# zumo_uni_spi_01.net
KiCad netlist of a schematic drawn in EAGLE
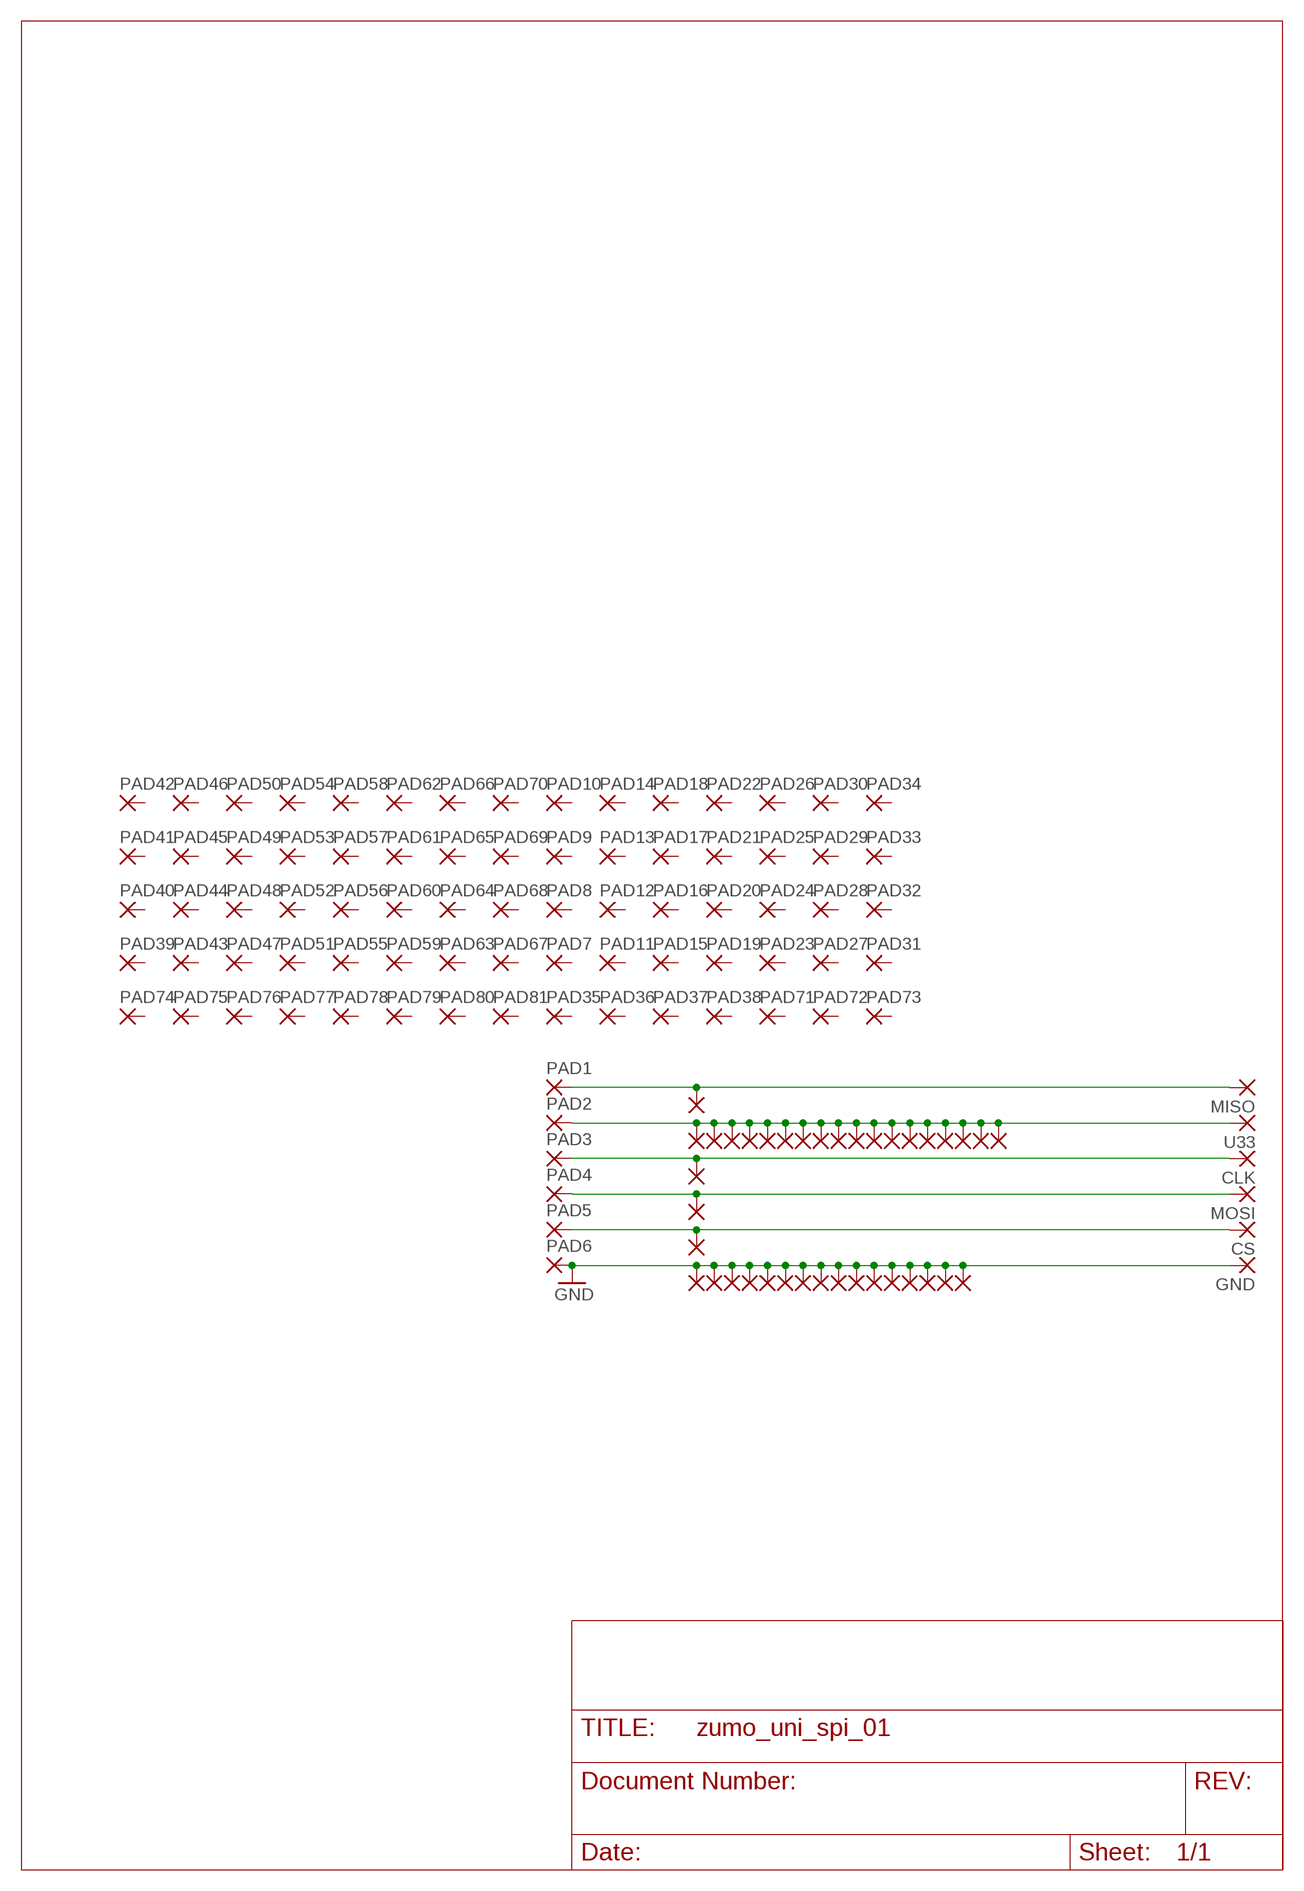
[diagram p0: schematic, sheet 1]

(export (version "E")
  (design (tool "Eeschema 10.0.6"))
  (components
    (comp (ref "CLK")
      (value "1,6/0,9")
      (footprint "eagle-import:1,6_0,9")
      (libsource (lib "eagle-import") (part "1,6/0,9"))
    )
    (comp (ref "CS")
      (value "1,6/0,9")
      (footprint "eagle-import:1,6_0,9")
      (libsource (lib "eagle-import") (part "1,6/0,9"))
    )
    (comp (ref "GND")
      (value "1,6/0,9")
      (footprint "eagle-import:1,6_0,9")
      (libsource (lib "eagle-import") (part "1,6/0,9"))
    )
    (comp (ref "MISO")
      (value "1,6/0,9")
      (footprint "eagle-import:1,6_0,9")
      (libsource (lib "eagle-import") (part "1,6/0,9"))
    )
    (comp (ref "MISO1")
      (value "1,6/0,9")
      (footprint "eagle-import:1,6_0,9")
      (libsource (lib "eagle-import") (part "1,6/0,9"))
    )
    (comp (ref "MISO2")
      (value "1,6/0,9")
      (footprint "eagle-import:1,6_0,9")
      (libsource (lib "eagle-import") (part "1,6/0,9"))
    )
    (comp (ref "MISO3")
      (value "1,6/0,9")
      (footprint "eagle-import:1,6_0,9")
      (libsource (lib "eagle-import") (part "1,6/0,9"))
    )
    (comp (ref "MISO4")
      (value "1,6/0,9")
      (footprint "eagle-import:1,6_0,9")
      (libsource (lib "eagle-import") (part "1,6/0,9"))
    )
    (comp (ref "MISO5")
      (value "1,6/0,9")
      (footprint "eagle-import:1,6_0,9")
      (libsource (lib "eagle-import") (part "1,6/0,9"))
    )
    (comp (ref "MISO6")
      (value "1,6/0,9")
      (footprint "eagle-import:1,6_0,9")
      (libsource (lib "eagle-import") (part "1,6/0,9"))
    )
    (comp (ref "MISO7")
      (value "1,6/0,9")
      (footprint "eagle-import:1,6_0,9")
      (libsource (lib "eagle-import") (part "1,6/0,9"))
    )
    (comp (ref "MISO8")
      (value "1,6/0,9")
      (footprint "eagle-import:1,6_0,9")
      (libsource (lib "eagle-import") (part "1,6/0,9"))
    )
    (comp (ref "MISO9")
      (value "1,6/0,9")
      (footprint "eagle-import:1,6_0,9")
      (libsource (lib "eagle-import") (part "1,6/0,9"))
    )
    (comp (ref "MISO10")
      (value "1,6/0,9")
      (footprint "eagle-import:1,6_0,9")
      (libsource (lib "eagle-import") (part "1,6/0,9"))
    )
    (comp (ref "MISO11")
      (value "1,6/0,9")
      (footprint "eagle-import:1,6_0,9")
      (libsource (lib "eagle-import") (part "1,6/0,9"))
    )
    (comp (ref "MISO12")
      (value "1,6/0,9")
      (footprint "eagle-import:1,6_0,9")
      (libsource (lib "eagle-import") (part "1,6/0,9"))
    )
    (comp (ref "MISO13")
      (value "1,6/0,9")
      (footprint "eagle-import:1,6_0,9")
      (libsource (lib "eagle-import") (part "1,6/0,9"))
    )
    (comp (ref "MISO14")
      (value "1,6/0,9")
      (footprint "eagle-import:1,6_0,9")
      (libsource (lib "eagle-import") (part "1,6/0,9"))
    )
    (comp (ref "MISO15")
      (value "1,6/0,9")
      (footprint "eagle-import:1,6_0,9")
      (libsource (lib "eagle-import") (part "1,6/0,9"))
    )
    (comp (ref "MISO16")
      (value "1,6/0,9")
      (footprint "eagle-import:1,6_0,9")
      (libsource (lib "eagle-import") (part "1,6/0,9"))
    )
    (comp (ref "MISO17")
      (value "1,6/0,9")
      (footprint "eagle-import:1,6_0,9")
      (libsource (lib "eagle-import") (part "1,6/0,9"))
    )
    (comp (ref "MISO18")
      (value "1,6/0,9")
      (footprint "eagle-import:1,6_0,9")
      (libsource (lib "eagle-import") (part "1,6/0,9"))
    )
    (comp (ref "MISO19")
      (value "1,6/0,9")
      (footprint "eagle-import:1,6_0,9")
      (libsource (lib "eagle-import") (part "1,6/0,9"))
    )
    (comp (ref "MISO20")
      (value "1,6/0,9")
      (footprint "eagle-import:1,6_0,9")
      (libsource (lib "eagle-import") (part "1,6/0,9"))
    )
    (comp (ref "MISO21")
      (value "1,6/0,9")
      (footprint "eagle-import:1,6_0,9")
      (libsource (lib "eagle-import") (part "1,6/0,9"))
    )
    (comp (ref "MISO22")
      (value "1,6/0,9")
      (footprint "eagle-import:1,6_0,9")
      (libsource (lib "eagle-import") (part "1,6/0,9"))
    )
    (comp (ref "MISO23")
      (value "1,6/0,9")
      (footprint "eagle-import:1,6_0,9")
      (libsource (lib "eagle-import") (part "1,6/0,9"))
    )
    (comp (ref "MISO24")
      (value "1,6/0,9")
      (footprint "eagle-import:1,6_0,9")
      (libsource (lib "eagle-import") (part "1,6/0,9"))
    )
    (comp (ref "MISO25")
      (value "1,6/0,9")
      (footprint "eagle-import:1,6_0,9")
      (libsource (lib "eagle-import") (part "1,6/0,9"))
    )
    (comp (ref "MISO26")
      (value "1,6/0,9")
      (footprint "eagle-import:1,6_0,9")
      (libsource (lib "eagle-import") (part "1,6/0,9"))
    )
    (comp (ref "MISO27")
      (value "1,6/0,9")
      (footprint "eagle-import:1,6_0,9")
      (libsource (lib "eagle-import") (part "1,6/0,9"))
    )
    (comp (ref "MISO28")
      (value "1,6/0,9")
      (footprint "eagle-import:1,6_0,9")
      (libsource (lib "eagle-import") (part "1,6/0,9"))
    )
    (comp (ref "MISO29")
      (value "1,6/0,9")
      (footprint "eagle-import:1,6_0,9")
      (libsource (lib "eagle-import") (part "1,6/0,9"))
    )
    (comp (ref "MISO30")
      (value "1,6/0,9")
      (footprint "eagle-import:1,6_0,9")
      (libsource (lib "eagle-import") (part "1,6/0,9"))
    )
    (comp (ref "MISO31")
      (value "1,6/0,9")
      (footprint "eagle-import:1,6_0,9")
      (libsource (lib "eagle-import") (part "1,6/0,9"))
    )
    (comp (ref "MISO32")
      (value "1,6/0,9")
      (footprint "eagle-import:1,6_0,9")
      (libsource (lib "eagle-import") (part "1,6/0,9"))
    )
    (comp (ref "MISO33")
      (value "1,6/0,9")
      (footprint "eagle-import:1,6_0,9")
      (libsource (lib "eagle-import") (part "1,6/0,9"))
    )
    (comp (ref "MISO34")
      (value "1,6/0,9")
      (footprint "eagle-import:1,6_0,9")
      (libsource (lib "eagle-import") (part "1,6/0,9"))
    )
    (comp (ref "MISO35")
      (value "1,6/0,9")
      (footprint "eagle-import:1,6_0,9")
      (libsource (lib "eagle-import") (part "1,6/0,9"))
    )
    (comp (ref "MISO36")
      (value "1,6/0,9")
      (footprint "eagle-import:1,6_0,9")
      (libsource (lib "eagle-import") (part "1,6/0,9"))
    )
    (comp (ref "MISO37")
      (value "1,6/0,9")
      (footprint "eagle-import:1,6_0,9")
      (libsource (lib "eagle-import") (part "1,6/0,9"))
    )
    (comp (ref "MISO38")
      (value "1,6/0,9")
      (footprint "eagle-import:1,6_0,9")
      (libsource (lib "eagle-import") (part "1,6/0,9"))
    )
    (comp (ref "MOSI")
      (value "1,6/0,9")
      (footprint "eagle-import:1,6_0,9")
      (libsource (lib "eagle-import") (part "1,6/0,9"))
    )
    (comp (ref "PAD1")
      (value "SMD2")
      (footprint "eagle-import:SMD1,27-2,54")
      (libsource (lib "eagle-import") (part "SMD2"))
    )
    (comp (ref "PAD2")
      (value "SMD2")
      (footprint "eagle-import:SMD1,27-2,54")
      (libsource (lib "eagle-import") (part "SMD2"))
    )
    (comp (ref "PAD3")
      (value "SMD2")
      (footprint "eagle-import:SMD1,27-2,54")
      (libsource (lib "eagle-import") (part "SMD2"))
    )
    (comp (ref "PAD4")
      (value "SMD2")
      (footprint "eagle-import:SMD1,27-2,54")
      (libsource (lib "eagle-import") (part "SMD2"))
    )
    (comp (ref "PAD5")
      (value "SMD2")
      (footprint "eagle-import:SMD1,27-2,54")
      (libsource (lib "eagle-import") (part "SMD2"))
    )
    (comp (ref "PAD6")
      (value "SMD2")
      (footprint "eagle-import:SMD1,27-2,54")
      (libsource (lib "eagle-import") (part "SMD2"))
    )
    (comp (ref "PAD7")
      (value "1,6/0,9")
      (footprint "eagle-import:1,6_0,9")
      (libsource (lib "eagle-import") (part "1,6/0,9"))
    )
    (comp (ref "PAD8")
      (value "1,6/0,9")
      (footprint "eagle-import:1,6_0,9")
      (libsource (lib "eagle-import") (part "1,6/0,9"))
    )
    (comp (ref "PAD9")
      (value "1,6/0,9")
      (footprint "eagle-import:1,6_0,9")
      (libsource (lib "eagle-import") (part "1,6/0,9"))
    )
    (comp (ref "PAD10")
      (value "1,6/0,9")
      (footprint "eagle-import:1,6_0,9")
      (libsource (lib "eagle-import") (part "1,6/0,9"))
    )
    (comp (ref "PAD11")
      (value "1,6/0,9")
      (footprint "eagle-import:1,6_0,9")
      (libsource (lib "eagle-import") (part "1,6/0,9"))
    )
    (comp (ref "PAD12")
      (value "1,6/0,9")
      (footprint "eagle-import:1,6_0,9")
      (libsource (lib "eagle-import") (part "1,6/0,9"))
    )
    (comp (ref "PAD13")
      (value "1,6/0,9")
      (footprint "eagle-import:1,6_0,9")
      (libsource (lib "eagle-import") (part "1,6/0,9"))
    )
    (comp (ref "PAD14")
      (value "1,6/0,9")
      (footprint "eagle-import:1,6_0,9")
      (libsource (lib "eagle-import") (part "1,6/0,9"))
    )
    (comp (ref "PAD15")
      (value "1,6/0,9")
      (footprint "eagle-import:1,6_0,9")
      (libsource (lib "eagle-import") (part "1,6/0,9"))
    )
    (comp (ref "PAD16")
      (value "1,6/0,9")
      (footprint "eagle-import:1,6_0,9")
      (libsource (lib "eagle-import") (part "1,6/0,9"))
    )
    (comp (ref "PAD17")
      (value "1,6/0,9")
      (footprint "eagle-import:1,6_0,9")
      (libsource (lib "eagle-import") (part "1,6/0,9"))
    )
    (comp (ref "PAD18")
      (value "1,6/0,9")
      (footprint "eagle-import:1,6_0,9")
      (libsource (lib "eagle-import") (part "1,6/0,9"))
    )
    (comp (ref "PAD19")
      (value "1,6/0,9")
      (footprint "eagle-import:1,6_0,9")
      (libsource (lib "eagle-import") (part "1,6/0,9"))
    )
    (comp (ref "PAD20")
      (value "1,6/0,9")
      (footprint "eagle-import:1,6_0,9")
      (libsource (lib "eagle-import") (part "1,6/0,9"))
    )
    (comp (ref "PAD21")
      (value "1,6/0,9")
      (footprint "eagle-import:1,6_0,9")
      (libsource (lib "eagle-import") (part "1,6/0,9"))
    )
    (comp (ref "PAD22")
      (value "1,6/0,9")
      (footprint "eagle-import:1,6_0,9")
      (libsource (lib "eagle-import") (part "1,6/0,9"))
    )
    (comp (ref "PAD23")
      (value "1,6/0,9")
      (footprint "eagle-import:1,6_0,9")
      (libsource (lib "eagle-import") (part "1,6/0,9"))
    )
    (comp (ref "PAD24")
      (value "1,6/0,9")
      (footprint "eagle-import:1,6_0,9")
      (libsource (lib "eagle-import") (part "1,6/0,9"))
    )
    (comp (ref "PAD25")
      (value "1,6/0,9")
      (footprint "eagle-import:1,6_0,9")
      (libsource (lib "eagle-import") (part "1,6/0,9"))
    )
    (comp (ref "PAD26")
      (value "1,6/0,9")
      (footprint "eagle-import:1,6_0,9")
      (libsource (lib "eagle-import") (part "1,6/0,9"))
    )
    (comp (ref "PAD27")
      (value "1,6/0,9")
      (footprint "eagle-import:1,6_0,9")
      (libsource (lib "eagle-import") (part "1,6/0,9"))
    )
    (comp (ref "PAD28")
      (value "1,6/0,9")
      (footprint "eagle-import:1,6_0,9")
      (libsource (lib "eagle-import") (part "1,6/0,9"))
    )
    (comp (ref "PAD29")
      (value "1,6/0,9")
      (footprint "eagle-import:1,6_0,9")
      (libsource (lib "eagle-import") (part "1,6/0,9"))
    )
    (comp (ref "PAD30")
      (value "1,6/0,9")
      (footprint "eagle-import:1,6_0,9")
      (libsource (lib "eagle-import") (part "1,6/0,9"))
    )
    (comp (ref "PAD31")
      (value "1,6/0,9")
      (footprint "eagle-import:1,6_0,9")
      (libsource (lib "eagle-import") (part "1,6/0,9"))
    )
    (comp (ref "PAD32")
      (value "1,6/0,9")
      (footprint "eagle-import:1,6_0,9")
      (libsource (lib "eagle-import") (part "1,6/0,9"))
    )
    (comp (ref "PAD33")
      (value "1,6/0,9")
      (footprint "eagle-import:1,6_0,9")
      (libsource (lib "eagle-import") (part "1,6/0,9"))
    )
    (comp (ref "PAD34")
      (value "1,6/0,9")
      (footprint "eagle-import:1,6_0,9")
      (libsource (lib "eagle-import") (part "1,6/0,9"))
    )
    (comp (ref "PAD35")
      (value "1,6/0,9")
      (footprint "eagle-import:1,6_0,9")
      (libsource (lib "eagle-import") (part "1,6/0,9"))
    )
    (comp (ref "PAD36")
      (value "1,6/0,9")
      (footprint "eagle-import:1,6_0,9")
      (libsource (lib "eagle-import") (part "1,6/0,9"))
    )
    (comp (ref "PAD37")
      (value "1,6/0,9")
      (footprint "eagle-import:1,6_0,9")
      (libsource (lib "eagle-import") (part "1,6/0,9"))
    )
    (comp (ref "PAD38")
      (value "1,6/0,9")
      (footprint "eagle-import:1,6_0,9")
      (libsource (lib "eagle-import") (part "1,6/0,9"))
    )
    (comp (ref "PAD39")
      (value "1,6/0,9")
      (footprint "eagle-import:1,6_0,9")
      (libsource (lib "eagle-import") (part "1,6/0,9"))
    )
    (comp (ref "PAD40")
      (value "1,6/0,9")
      (footprint "eagle-import:1,6_0,9")
      (libsource (lib "eagle-import") (part "1,6/0,9"))
    )
    (comp (ref "PAD41")
      (value "1,6/0,9")
      (footprint "eagle-import:1,6_0,9")
      (libsource (lib "eagle-import") (part "1,6/0,9"))
    )
    (comp (ref "PAD42")
      (value "1,6/0,9")
      (footprint "eagle-import:1,6_0,9")
      (libsource (lib "eagle-import") (part "1,6/0,9"))
    )
    (comp (ref "PAD43")
      (value "1,6/0,9")
      (footprint "eagle-import:1,6_0,9")
      (libsource (lib "eagle-import") (part "1,6/0,9"))
    )
    (comp (ref "PAD44")
      (value "1,6/0,9")
      (footprint "eagle-import:1,6_0,9")
      (libsource (lib "eagle-import") (part "1,6/0,9"))
    )
    (comp (ref "PAD45")
      (value "1,6/0,9")
      (footprint "eagle-import:1,6_0,9")
      (libsource (lib "eagle-import") (part "1,6/0,9"))
    )
    (comp (ref "PAD46")
      (value "1,6/0,9")
      (footprint "eagle-import:1,6_0,9")
      (libsource (lib "eagle-import") (part "1,6/0,9"))
    )
    (comp (ref "PAD47")
      (value "1,6/0,9")
      (footprint "eagle-import:1,6_0,9")
      (libsource (lib "eagle-import") (part "1,6/0,9"))
    )
    (comp (ref "PAD48")
      (value "1,6/0,9")
      (footprint "eagle-import:1,6_0,9")
      (libsource (lib "eagle-import") (part "1,6/0,9"))
    )
    (comp (ref "PAD49")
      (value "1,6/0,9")
      (footprint "eagle-import:1,6_0,9")
      (libsource (lib "eagle-import") (part "1,6/0,9"))
    )
    (comp (ref "PAD50")
      (value "1,6/0,9")
      (footprint "eagle-import:1,6_0,9")
      (libsource (lib "eagle-import") (part "1,6/0,9"))
    )
    (comp (ref "PAD51")
      (value "1,6/0,9")
      (footprint "eagle-import:1,6_0,9")
      (libsource (lib "eagle-import") (part "1,6/0,9"))
    )
    (comp (ref "PAD52")
      (value "1,6/0,9")
      (footprint "eagle-import:1,6_0,9")
      (libsource (lib "eagle-import") (part "1,6/0,9"))
    )
    (comp (ref "PAD53")
      (value "1,6/0,9")
      (footprint "eagle-import:1,6_0,9")
      (libsource (lib "eagle-import") (part "1,6/0,9"))
    )
    (comp (ref "PAD54")
      (value "1,6/0,9")
      (footprint "eagle-import:1,6_0,9")
      (libsource (lib "eagle-import") (part "1,6/0,9"))
    )
    (comp (ref "PAD55")
      (value "1,6/0,9")
      (footprint "eagle-import:1,6_0,9")
      (libsource (lib "eagle-import") (part "1,6/0,9"))
    )
    (comp (ref "PAD56")
      (value "1,6/0,9")
      (footprint "eagle-import:1,6_0,9")
      (libsource (lib "eagle-import") (part "1,6/0,9"))
    )
    (comp (ref "PAD57")
      (value "1,6/0,9")
      (footprint "eagle-import:1,6_0,9")
      (libsource (lib "eagle-import") (part "1,6/0,9"))
    )
    (comp (ref "PAD58")
      (value "1,6/0,9")
      (footprint "eagle-import:1,6_0,9")
      (libsource (lib "eagle-import") (part "1,6/0,9"))
    )
    (comp (ref "PAD59")
      (value "1,6/0,9")
      (footprint "eagle-import:1,6_0,9")
      (libsource (lib "eagle-import") (part "1,6/0,9"))
    )
    (comp (ref "PAD60")
      (value "1,6/0,9")
      (footprint "eagle-import:1,6_0,9")
      (libsource (lib "eagle-import") (part "1,6/0,9"))
    )
    (comp (ref "PAD61")
      (value "1,6/0,9")
      (footprint "eagle-import:1,6_0,9")
      (libsource (lib "eagle-import") (part "1,6/0,9"))
    )
    (comp (ref "PAD62")
      (value "1,6/0,9")
      (footprint "eagle-import:1,6_0,9")
      (libsource (lib "eagle-import") (part "1,6/0,9"))
    )
    (comp (ref "PAD63")
      (value "1,6/0,9")
      (footprint "eagle-import:1,6_0,9")
      (libsource (lib "eagle-import") (part "1,6/0,9"))
    )
    (comp (ref "PAD64")
      (value "1,6/0,9")
      (footprint "eagle-import:1,6_0,9")
      (libsource (lib "eagle-import") (part "1,6/0,9"))
    )
    (comp (ref "PAD65")
      (value "1,6/0,9")
      (footprint "eagle-import:1,6_0,9")
      (libsource (lib "eagle-import") (part "1,6/0,9"))
    )
    (comp (ref "PAD66")
      (value "1,6/0,9")
      (footprint "eagle-import:1,6_0,9")
      (libsource (lib "eagle-import") (part "1,6/0,9"))
    )
    (comp (ref "PAD67")
      (value "1,6/0,9")
      (footprint "eagle-import:1,6_0,9")
      (libsource (lib "eagle-import") (part "1,6/0,9"))
    )
    (comp (ref "PAD68")
      (value "1,6/0,9")
      (footprint "eagle-import:1,6_0,9")
      (libsource (lib "eagle-import") (part "1,6/0,9"))
    )
    (comp (ref "PAD69")
      (value "1,6/0,9")
      (footprint "eagle-import:1,6_0,9")
      (libsource (lib "eagle-import") (part "1,6/0,9"))
    )
    (comp (ref "PAD70")
      (value "1,6/0,9")
      (footprint "eagle-import:1,6_0,9")
      (libsource (lib "eagle-import") (part "1,6/0,9"))
    )
    (comp (ref "PAD71")
      (value "1,6/0,9")
      (footprint "eagle-import:1,6_0,9")
      (libsource (lib "eagle-import") (part "1,6/0,9"))
    )
    (comp (ref "PAD72")
      (value "1,6/0,9")
      (footprint "eagle-import:1,6_0,9")
      (libsource (lib "eagle-import") (part "1,6/0,9"))
    )
    (comp (ref "PAD73")
      (value "1,6/0,9")
      (footprint "eagle-import:1,6_0,9")
      (libsource (lib "eagle-import") (part "1,6/0,9"))
    )
    (comp (ref "PAD74")
      (value "1,6/0,9")
      (footprint "eagle-import:1,6_0,9")
      (libsource (lib "eagle-import") (part "1,6/0,9"))
    )
    (comp (ref "PAD75")
      (value "1,6/0,9")
      (footprint "eagle-import:1,6_0,9")
      (libsource (lib "eagle-import") (part "1,6/0,9"))
    )
    (comp (ref "PAD76")
      (value "1,6/0,9")
      (footprint "eagle-import:1,6_0,9")
      (libsource (lib "eagle-import") (part "1,6/0,9"))
    )
    (comp (ref "PAD77")
      (value "1,6/0,9")
      (footprint "eagle-import:1,6_0,9")
      (libsource (lib "eagle-import") (part "1,6/0,9"))
    )
    (comp (ref "PAD78")
      (value "1,6/0,9")
      (footprint "eagle-import:1,6_0,9")
      (libsource (lib "eagle-import") (part "1,6/0,9"))
    )
    (comp (ref "PAD79")
      (value "1,6/0,9")
      (footprint "eagle-import:1,6_0,9")
      (libsource (lib "eagle-import") (part "1,6/0,9"))
    )
    (comp (ref "PAD80")
      (value "1,6/0,9")
      (footprint "eagle-import:1,6_0,9")
      (libsource (lib "eagle-import") (part "1,6/0,9"))
    )
    (comp (ref "PAD81")
      (value "1,6/0,9")
      (footprint "eagle-import:1,6_0,9")
      (libsource (lib "eagle-import") (part "1,6/0,9"))
    )
    (comp (ref "U33")
      (value "1,6/0,9")
      (footprint "eagle-import:1,6_0,9")
      (libsource (lib "eagle-import") (part "1,6/0,9"))
    )
  )
  (nets
    (net (code "1") (name "GND") (class "Default")
      (node (ref "GND") (pin "1") (pinfunction "P_1") (pintype "passive"))
      (node (ref "MISO10") (pin "1") (pinfunction "P_1") (pintype "passive"))
      (node (ref "MISO11") (pin "1") (pinfunction "P_1") (pintype "passive"))
      (node (ref "MISO12") (pin "1") (pinfunction "P_1") (pintype "passive"))
      (node (ref "MISO13") (pin "1") (pinfunction "P_1") (pintype "passive"))
      (node (ref "MISO14") (pin "1") (pinfunction "P_1") (pintype "passive"))
      (node (ref "MISO15") (pin "1") (pinfunction "P_1") (pintype "passive"))
      (node (ref "MISO16") (pin "1") (pinfunction "P_1") (pintype "passive"))
      (node (ref "MISO17") (pin "1") (pinfunction "P_1") (pintype "passive"))
      (node (ref "MISO18") (pin "1") (pinfunction "P_1") (pintype "passive"))
      (node (ref "MISO19") (pin "1") (pinfunction "P_1") (pintype "passive"))
      (node (ref "MISO20") (pin "1") (pinfunction "P_1") (pintype "passive"))
      (node (ref "MISO5") (pin "1") (pinfunction "P_1") (pintype "passive"))
      (node (ref "MISO6") (pin "1") (pinfunction "P_1") (pintype "passive"))
      (node (ref "MISO7") (pin "1") (pinfunction "P_1") (pintype "passive"))
      (node (ref "MISO8") (pin "1") (pinfunction "P_1") (pintype "passive"))
      (node (ref "MISO9") (pin "1") (pinfunction "P_1") (pintype "passive"))
      (node (ref "PAD6") (pin "1") (pinfunction "P_1") (pintype "passive"))
    )
    (net (code "2") (name "Net-(CLK-P)") (class "Default")
      (node (ref "CLK") (pin "1") (pinfunction "P_1") (pintype "passive"))
      (node (ref "MISO3") (pin "1") (pinfunction "P_1") (pintype "passive"))
      (node (ref "PAD3") (pin "1") (pinfunction "P_1") (pintype "passive"))
    )
    (net (code "3") (name "Net-(CS-P)") (class "Default")
      (node (ref "CS") (pin "1") (pinfunction "P_1") (pintype "passive"))
      (node (ref "MISO1") (pin "1") (pinfunction "P_1") (pintype "passive"))
      (node (ref "PAD5") (pin "1") (pinfunction "P_1") (pintype "passive"))
    )
    (net (code "4") (name "Net-(MISO-P)") (class "Default")
      (node (ref "MISO") (pin "1") (pinfunction "P_1") (pintype "passive"))
      (node (ref "MISO21") (pin "1") (pinfunction "P_1") (pintype "passive"))
      (node (ref "PAD1") (pin "1") (pinfunction "P_1") (pintype "passive"))
    )
    (net (code "5") (name "Net-(MISO2-P)") (class "Default")
      (node (ref "MISO2") (pin "1") (pinfunction "P_1") (pintype "passive"))
      (node (ref "MOSI") (pin "1") (pinfunction "P_1") (pintype "passive"))
      (node (ref "PAD4") (pin "1") (pinfunction "P_1") (pintype "passive"))
    )
    (net (code "6") (name "Net-(MISO22-P)") (class "Default")
      (node (ref "MISO22") (pin "1") (pinfunction "P_1") (pintype "passive"))
      (node (ref "MISO23") (pin "1") (pinfunction "P_1") (pintype "passive"))
      (node (ref "MISO24") (pin "1") (pinfunction "P_1") (pintype "passive"))
      (node (ref "MISO25") (pin "1") (pinfunction "P_1") (pintype "passive"))
      (node (ref "MISO26") (pin "1") (pinfunction "P_1") (pintype "passive"))
      (node (ref "MISO27") (pin "1") (pinfunction "P_1") (pintype "passive"))
      (node (ref "MISO28") (pin "1") (pinfunction "P_1") (pintype "passive"))
      (node (ref "MISO29") (pin "1") (pinfunction "P_1") (pintype "passive"))
      (node (ref "MISO30") (pin "1") (pinfunction "P_1") (pintype "passive"))
      (node (ref "MISO31") (pin "1") (pinfunction "P_1") (pintype "passive"))
      (node (ref "MISO32") (pin "1") (pinfunction "P_1") (pintype "passive"))
      (node (ref "MISO33") (pin "1") (pinfunction "P_1") (pintype "passive"))
      (node (ref "MISO34") (pin "1") (pinfunction "P_1") (pintype "passive"))
      (node (ref "MISO35") (pin "1") (pinfunction "P_1") (pintype "passive"))
      (node (ref "MISO36") (pin "1") (pinfunction "P_1") (pintype "passive"))
      (node (ref "MISO37") (pin "1") (pinfunction "P_1") (pintype "passive"))
      (node (ref "MISO38") (pin "1") (pinfunction "P_1") (pintype "passive"))
      (node (ref "MISO4") (pin "1") (pinfunction "P_1") (pintype "passive"))
      (node (ref "PAD2") (pin "1") (pinfunction "P_1") (pintype "passive"))
      (node (ref "U33") (pin "1") (pinfunction "P_1") (pintype "passive"))
    )
    (net (code "7") (name "unconnected-(PAD7-P-Pad1)") (class "Default")
      (node (ref "PAD7") (pin "1") (pinfunction "P_1") (pintype "passive"))
    )
    (net (code "8") (name "unconnected-(PAD8-P-Pad1)") (class "Default")
      (node (ref "PAD8") (pin "1") (pinfunction "P_1") (pintype "passive"))
    )
    (net (code "9") (name "unconnected-(PAD9-P-Pad1)") (class "Default")
      (node (ref "PAD9") (pin "1") (pinfunction "P_1") (pintype "passive"))
    )
    (net (code "10") (name "unconnected-(PAD10-P-Pad1)") (class "Default")
      (node (ref "PAD10") (pin "1") (pinfunction "P_1") (pintype "passive"))
    )
    (net (code "11") (name "unconnected-(PAD11-P-Pad1)") (class "Default")
      (node (ref "PAD11") (pin "1") (pinfunction "P_1") (pintype "passive"))
    )
    (net (code "12") (name "unconnected-(PAD12-P-Pad1)") (class "Default")
      (node (ref "PAD12") (pin "1") (pinfunction "P_1") (pintype "passive"))
    )
    (net (code "13") (name "unconnected-(PAD13-P-Pad1)") (class "Default")
      (node (ref "PAD13") (pin "1") (pinfunction "P_1") (pintype "passive"))
    )
    (net (code "14") (name "unconnected-(PAD14-P-Pad1)") (class "Default")
      (node (ref "PAD14") (pin "1") (pinfunction "P_1") (pintype "passive"))
    )
    (net (code "15") (name "unconnected-(PAD15-P-Pad1)") (class "Default")
      (node (ref "PAD15") (pin "1") (pinfunction "P_1") (pintype "passive"))
    )
    (net (code "16") (name "unconnected-(PAD16-P-Pad1)") (class "Default")
      (node (ref "PAD16") (pin "1") (pinfunction "P_1") (pintype "passive"))
    )
    (net (code "17") (name "unconnected-(PAD17-P-Pad1)") (class "Default")
      (node (ref "PAD17") (pin "1") (pinfunction "P_1") (pintype "passive"))
    )
    (net (code "18") (name "unconnected-(PAD18-P-Pad1)") (class "Default")
      (node (ref "PAD18") (pin "1") (pinfunction "P_1") (pintype "passive"))
    )
    (net (code "19") (name "unconnected-(PAD19-P-Pad1)") (class "Default")
      (node (ref "PAD19") (pin "1") (pinfunction "P_1") (pintype "passive"))
    )
    (net (code "20") (name "unconnected-(PAD20-P-Pad1)") (class "Default")
      (node (ref "PAD20") (pin "1") (pinfunction "P_1") (pintype "passive"))
    )
    (net (code "21") (name "unconnected-(PAD21-P-Pad1)") (class "Default")
      (node (ref "PAD21") (pin "1") (pinfunction "P_1") (pintype "passive"))
    )
    (net (code "22") (name "unconnected-(PAD22-P-Pad1)") (class "Default")
      (node (ref "PAD22") (pin "1") (pinfunction "P_1") (pintype "passive"))
    )
    (net (code "23") (name "unconnected-(PAD23-P-Pad1)") (class "Default")
      (node (ref "PAD23") (pin "1") (pinfunction "P_1") (pintype "passive"))
    )
    (net (code "24") (name "unconnected-(PAD24-P-Pad1)") (class "Default")
      (node (ref "PAD24") (pin "1") (pinfunction "P_1") (pintype "passive"))
    )
    (net (code "25") (name "unconnected-(PAD25-P-Pad1)") (class "Default")
      (node (ref "PAD25") (pin "1") (pinfunction "P_1") (pintype "passive"))
    )
    (net (code "26") (name "unconnected-(PAD26-P-Pad1)") (class "Default")
      (node (ref "PAD26") (pin "1") (pinfunction "P_1") (pintype "passive"))
    )
    (net (code "27") (name "unconnected-(PAD27-P-Pad1)") (class "Default")
      (node (ref "PAD27") (pin "1") (pinfunction "P_1") (pintype "passive"))
    )
    (net (code "28") (name "unconnected-(PAD28-P-Pad1)") (class "Default")
      (node (ref "PAD28") (pin "1") (pinfunction "P_1") (pintype "passive"))
    )
    (net (code "29") (name "unconnected-(PAD29-P-Pad1)") (class "Default")
      (node (ref "PAD29") (pin "1") (pinfunction "P_1") (pintype "passive"))
    )
    (net (code "30") (name "unconnected-(PAD30-P-Pad1)") (class "Default")
      (node (ref "PAD30") (pin "1") (pinfunction "P_1") (pintype "passive"))
    )
    (net (code "31") (name "unconnected-(PAD31-P-Pad1)") (class "Default")
      (node (ref "PAD31") (pin "1") (pinfunction "P_1") (pintype "passive"))
    )
    (net (code "32") (name "unconnected-(PAD32-P-Pad1)") (class "Default")
      (node (ref "PAD32") (pin "1") (pinfunction "P_1") (pintype "passive"))
    )
    (net (code "33") (name "unconnected-(PAD33-P-Pad1)") (class "Default")
      (node (ref "PAD33") (pin "1") (pinfunction "P_1") (pintype "passive"))
    )
    (net (code "34") (name "unconnected-(PAD34-P-Pad1)") (class "Default")
      (node (ref "PAD34") (pin "1") (pinfunction "P_1") (pintype "passive"))
    )
    (net (code "35") (name "unconnected-(PAD35-P-Pad1)") (class "Default")
      (node (ref "PAD35") (pin "1") (pinfunction "P_1") (pintype "passive"))
    )
    (net (code "36") (name "unconnected-(PAD36-P-Pad1)") (class "Default")
      (node (ref "PAD36") (pin "1") (pinfunction "P_1") (pintype "passive"))
    )
    (net (code "37") (name "unconnected-(PAD37-P-Pad1)") (class "Default")
      (node (ref "PAD37") (pin "1") (pinfunction "P_1") (pintype "passive"))
    )
    (net (code "38") (name "unconnected-(PAD38-P-Pad1)") (class "Default")
      (node (ref "PAD38") (pin "1") (pinfunction "P_1") (pintype "passive"))
    )
    (net (code "39") (name "unconnected-(PAD39-P-Pad1)") (class "Default")
      (node (ref "PAD39") (pin "1") (pinfunction "P_1") (pintype "passive"))
    )
    (net (code "40") (name "unconnected-(PAD40-P-Pad1)") (class "Default")
      (node (ref "PAD40") (pin "1") (pinfunction "P_1") (pintype "passive"))
    )
    (net (code "41") (name "unconnected-(PAD41-P-Pad1)") (class "Default")
      (node (ref "PAD41") (pin "1") (pinfunction "P_1") (pintype "passive"))
    )
    (net (code "42") (name "unconnected-(PAD42-P-Pad1)") (class "Default")
      (node (ref "PAD42") (pin "1") (pinfunction "P_1") (pintype "passive"))
    )
    (net (code "43") (name "unconnected-(PAD43-P-Pad1)") (class "Default")
      (node (ref "PAD43") (pin "1") (pinfunction "P_1") (pintype "passive"))
    )
    (net (code "44") (name "unconnected-(PAD44-P-Pad1)") (class "Default")
      (node (ref "PAD44") (pin "1") (pinfunction "P_1") (pintype "passive"))
    )
    (net (code "45") (name "unconnected-(PAD45-P-Pad1)") (class "Default")
      (node (ref "PAD45") (pin "1") (pinfunction "P_1") (pintype "passive"))
    )
    (net (code "46") (name "unconnected-(PAD46-P-Pad1)") (class "Default")
      (node (ref "PAD46") (pin "1") (pinfunction "P_1") (pintype "passive"))
    )
    (net (code "47") (name "unconnected-(PAD47-P-Pad1)") (class "Default")
      (node (ref "PAD47") (pin "1") (pinfunction "P_1") (pintype "passive"))
    )
    (net (code "48") (name "unconnected-(PAD48-P-Pad1)") (class "Default")
      (node (ref "PAD48") (pin "1") (pinfunction "P_1") (pintype "passive"))
    )
    (net (code "49") (name "unconnected-(PAD49-P-Pad1)") (class "Default")
      (node (ref "PAD49") (pin "1") (pinfunction "P_1") (pintype "passive"))
    )
    (net (code "50") (name "unconnected-(PAD50-P-Pad1)") (class "Default")
      (node (ref "PAD50") (pin "1") (pinfunction "P_1") (pintype "passive"))
    )
    (net (code "51") (name "unconnected-(PAD51-P-Pad1)") (class "Default")
      (node (ref "PAD51") (pin "1") (pinfunction "P_1") (pintype "passive"))
    )
    (net (code "52") (name "unconnected-(PAD52-P-Pad1)") (class "Default")
      (node (ref "PAD52") (pin "1") (pinfunction "P_1") (pintype "passive"))
    )
    (net (code "53") (name "unconnected-(PAD53-P-Pad1)") (class "Default")
      (node (ref "PAD53") (pin "1") (pinfunction "P_1") (pintype "passive"))
    )
    (net (code "54") (name "unconnected-(PAD54-P-Pad1)") (class "Default")
      (node (ref "PAD54") (pin "1") (pinfunction "P_1") (pintype "passive"))
    )
    (net (code "55") (name "unconnected-(PAD55-P-Pad1)") (class "Default")
      (node (ref "PAD55") (pin "1") (pinfunction "P_1") (pintype "passive"))
    )
    (net (code "56") (name "unconnected-(PAD56-P-Pad1)") (class "Default")
      (node (ref "PAD56") (pin "1") (pinfunction "P_1") (pintype "passive"))
    )
    (net (code "57") (name "unconnected-(PAD57-P-Pad1)") (class "Default")
      (node (ref "PAD57") (pin "1") (pinfunction "P_1") (pintype "passive"))
    )
    (net (code "58") (name "unconnected-(PAD58-P-Pad1)") (class "Default")
      (node (ref "PAD58") (pin "1") (pinfunction "P_1") (pintype "passive"))
    )
    (net (code "59") (name "unconnected-(PAD59-P-Pad1)") (class "Default")
      (node (ref "PAD59") (pin "1") (pinfunction "P_1") (pintype "passive"))
    )
    (net (code "60") (name "unconnected-(PAD60-P-Pad1)") (class "Default")
      (node (ref "PAD60") (pin "1") (pinfunction "P_1") (pintype "passive"))
    )
    (net (code "61") (name "unconnected-(PAD61-P-Pad1)") (class "Default")
      (node (ref "PAD61") (pin "1") (pinfunction "P_1") (pintype "passive"))
    )
    (net (code "62") (name "unconnected-(PAD62-P-Pad1)") (class "Default")
      (node (ref "PAD62") (pin "1") (pinfunction "P_1") (pintype "passive"))
    )
    (net (code "63") (name "unconnected-(PAD63-P-Pad1)") (class "Default")
      (node (ref "PAD63") (pin "1") (pinfunction "P_1") (pintype "passive"))
    )
    (net (code "64") (name "unconnected-(PAD64-P-Pad1)") (class "Default")
      (node (ref "PAD64") (pin "1") (pinfunction "P_1") (pintype "passive"))
    )
    (net (code "65") (name "unconnected-(PAD65-P-Pad1)") (class "Default")
      (node (ref "PAD65") (pin "1") (pinfunction "P_1") (pintype "passive"))
    )
    (net (code "66") (name "unconnected-(PAD66-P-Pad1)") (class "Default")
      (node (ref "PAD66") (pin "1") (pinfunction "P_1") (pintype "passive"))
    )
    (net (code "67") (name "unconnected-(PAD67-P-Pad1)") (class "Default")
      (node (ref "PAD67") (pin "1") (pinfunction "P_1") (pintype "passive"))
    )
    (net (code "68") (name "unconnected-(PAD68-P-Pad1)") (class "Default")
      (node (ref "PAD68") (pin "1") (pinfunction "P_1") (pintype "passive"))
    )
    (net (code "69") (name "unconnected-(PAD69-P-Pad1)") (class "Default")
      (node (ref "PAD69") (pin "1") (pinfunction "P_1") (pintype "passive"))
    )
    (net (code "70") (name "unconnected-(PAD70-P-Pad1)") (class "Default")
      (node (ref "PAD70") (pin "1") (pinfunction "P_1") (pintype "passive"))
    )
    (net (code "71") (name "unconnected-(PAD71-P-Pad1)") (class "Default")
      (node (ref "PAD71") (pin "1") (pinfunction "P_1") (pintype "passive"))
    )
    (net (code "72") (name "unconnected-(PAD72-P-Pad1)") (class "Default")
      (node (ref "PAD72") (pin "1") (pinfunction "P_1") (pintype "passive"))
    )
    (net (code "73") (name "unconnected-(PAD73-P-Pad1)") (class "Default")
      (node (ref "PAD73") (pin "1") (pinfunction "P_1") (pintype "passive"))
    )
    (net (code "74") (name "unconnected-(PAD74-P-Pad1)") (class "Default")
      (node (ref "PAD74") (pin "1") (pinfunction "P_1") (pintype "passive"))
    )
    (net (code "75") (name "unconnected-(PAD75-P-Pad1)") (class "Default")
      (node (ref "PAD75") (pin "1") (pinfunction "P_1") (pintype "passive"))
    )
    (net (code "76") (name "unconnected-(PAD76-P-Pad1)") (class "Default")
      (node (ref "PAD76") (pin "1") (pinfunction "P_1") (pintype "passive"))
    )
    (net (code "77") (name "unconnected-(PAD77-P-Pad1)") (class "Default")
      (node (ref "PAD77") (pin "1") (pinfunction "P_1") (pintype "passive"))
    )
    (net (code "78") (name "unconnected-(PAD78-P-Pad1)") (class "Default")
      (node (ref "PAD78") (pin "1") (pinfunction "P_1") (pintype "passive"))
    )
    (net (code "79") (name "unconnected-(PAD79-P-Pad1)") (class "Default")
      (node (ref "PAD79") (pin "1") (pinfunction "P_1") (pintype "passive"))
    )
    (net (code "80") (name "unconnected-(PAD80-P-Pad1)") (class "Default")
      (node (ref "PAD80") (pin "1") (pinfunction "P_1") (pintype "passive"))
    )
    (net (code "81") (name "unconnected-(PAD81-P-Pad1)") (class "Default")
      (node (ref "PAD81") (pin "1") (pinfunction "P_1") (pintype "passive"))
    )
  )
)
